# Wifi.net
KiCad netlist of a schematic drawn in Altium Designer
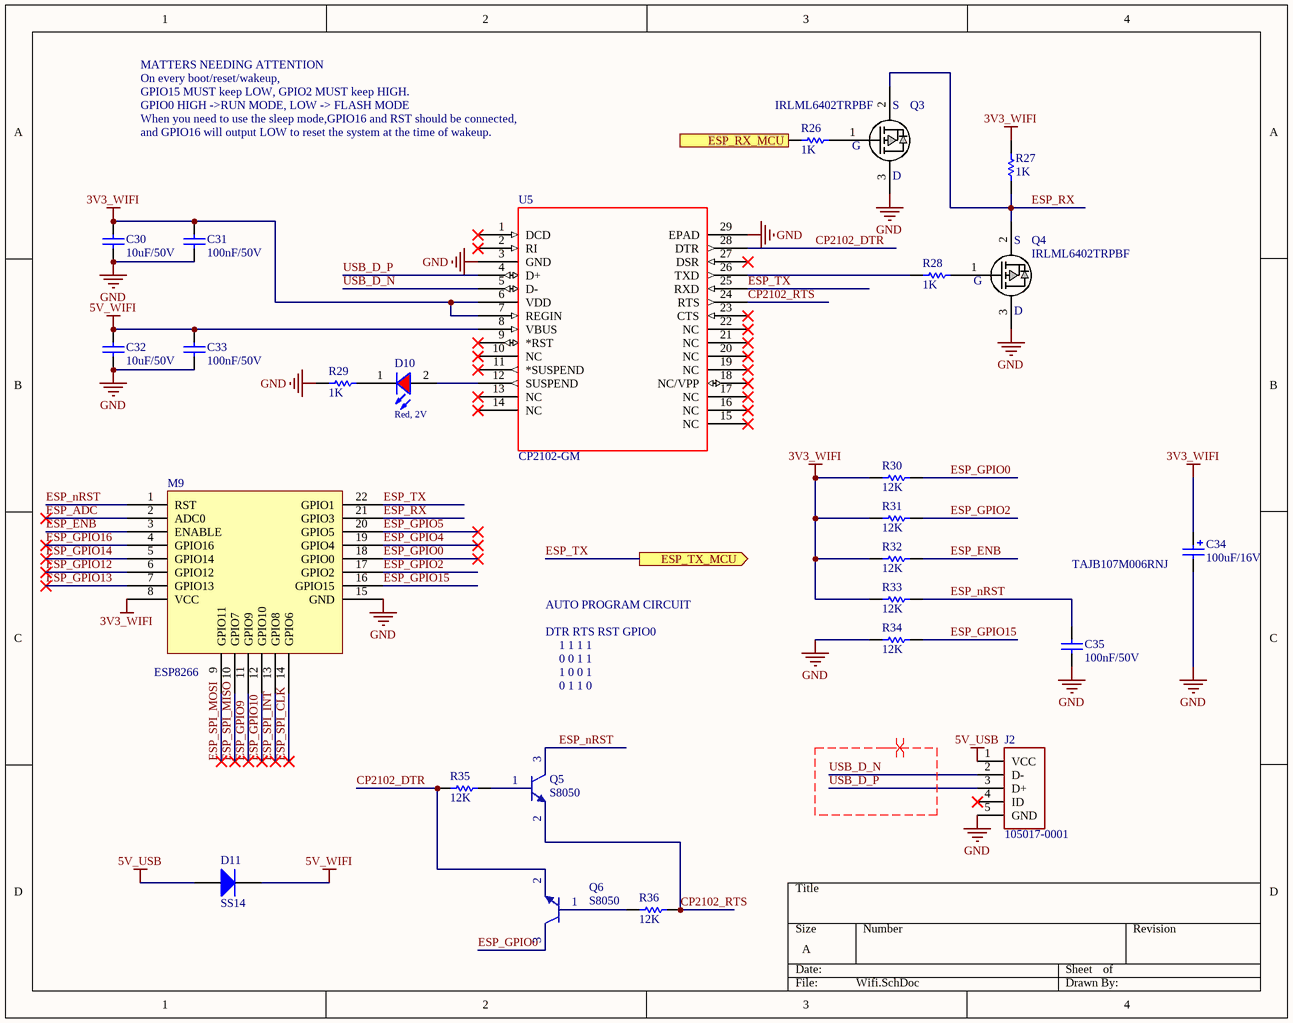
[diagram p0: Wifi.SchDoc]

(export (version "E")
  (design (tool "Eeschema 10.0.6"))
  (components
    (comp (ref "C30")
      (value "10uF/50V")
      (footprint "CAP-SM-0805")
      (description "CAP CER 10UF 50V X5R 0805")
      (fields
        (field (name "MANUFACTURER") "Yageo")
        (field (name "MANUFACTURER PART NUMBER") "CC0805KKX5R9BB106")
      )
      (libsource (lib "Capacitor") (part "Cap-10uF-50V-0805"))
    )
    (comp (ref "C31")
      (value "100nF/50V")
      (footprint "CAP-SM-0805")
      (description "CAP CER 0.1UF 50V Y5V 0805")
      (fields
        (field (name "MANUFACTURER") "Samsung Electro-Mechanics")
        (field (name "MANUFACTURER PART NUMBER") "CL21F104ZBCNNNC")
      )
      (libsource (lib "Capacitor") (part "Cap-100nF-50V-0805"))
    )
    (comp (ref "C32")
      (value "10uF/50V")
      (footprint "CAP-SM-0805")
      (description "CAP CER 10UF 50V X5R 0805")
      (fields
        (field (name "MANUFACTURER") "Yageo")
        (field (name "MANUFACTURER PART NUMBER") "CC0805KKX5R9BB106")
      )
      (libsource (lib "Capacitor") (part "Cap-10uF-50V-0805"))
    )
    (comp (ref "C33")
      (value "100nF/50V")
      (footprint "CAP-SM-0805")
      (description "CAP CER 0.1UF 50V Y5V 0805")
      (fields
        (field (name "MANUFACTURER") "Samsung Electro-Mechanics")
        (field (name "MANUFACTURER PART NUMBER") "CL21F104ZBCNNNC")
      )
      (libsource (lib "Capacitor") (part "Cap-100nF-50V-0805"))
    )
    (comp (ref "C34")
      (value "100uF/16V")
      (footprint "CAP_SM_TAN")
      (fields
        (field (name "MANUFACTURER") "Nichicon")
        (field (name "MANUFACTURER PART NUMBER") "UWX1C101MCL1GB")
        (field (name "Comment") "TAJB107M006RNJ")
      )
      (libsource (lib "Capacitor") (part "Cap-Tan-100uF-16V"))
    )
    (comp (ref "C35")
      (value "100nF/50V")
      (footprint "CAP-SM-0805")
      (description "CAP CER 0.1UF 50V Y5V 0805")
      (fields
        (field (name "MANUFACTURER") "Samsung Electro-Mechanics")
        (field (name "MANUFACTURER PART NUMBER") "CL21F104ZBCNNNC")
      )
      (libsource (lib "Capacitor") (part "Cap-100nF-50V-0805"))
    )
    (comp (ref "D10")
      (value "Red, 2V")
      (footprint "WL-SMCW_0805")
      (description "WL-SMCW SMT Mono-color Chip LED Waterclear, size 0805, Red, 2V, 140deg")
      (fields (field (name "PART NUMBER") "150080RS75000") (field (name "PUBLISHER") "Wurth Elektronik"))
      (libsource (lib "150080BS75000_Altium_WL-SMCW_rev20a") (part "150080RS75000"))
    )
    (comp (ref "D11")
      (value "SS14")
      (footprint "SS14")
      (description "DIODE SCHOTTKY 40V 1A SMA")
      (fields (field (name "MANUFACTURER") "ON Semiconductor"))
      (libsource (lib "Diode") (part "Diode-SS14"))
    )
    (comp (ref "J2")
      (value "105017-0001")
      (footprint "CONN_105017-0001")
      (description "No Description Available")
      (fields (field (name "COPYRIGHT") "Copyright (C) 2018 Accelerated Designs. All rights reserved"))
      (libsource (lib "Header-connector") (part "105017-0001"))
    )
    (comp (ref "M9") (value "ESP8266") (footprint "ESP8266") (libsource (lib "chicken") (part "ESP8266")))
    (comp (ref "Q3")
      (value "IRLML6402TRPBF")
      (footprint "SOT23_NEX")
      (description "P-Channel 20V 3.7A (Ta) 1.3W (Ta) Surface Mount Micro3™/SOT-23")
      (libsource (lib "MOSFET") (part "IRLML6402TRPBF"))
    )
    (comp (ref "Q4")
      (value "IRLML6402TRPBF")
      (footprint "SOT23_NEX")
      (description "P-Channel 20V 3.7A (Ta) 1.3W (Ta) Surface Mount Micro3™/SOT-23")
      (libsource (lib "MOSFET") (part "IRLML6402TRPBF"))
    )
    (comp (ref "Q5") (value "S8050") (footprint "SOT23_NEX") (libsource (lib "BJT") (part "S8050")))
    (comp (ref "Q6") (value "S8050") (footprint "SOT23_NEX") (libsource (lib "BJT") (part "S8050")))
    (comp (ref "R26")
      (value "1K")
      (footprint "Resistor:RES-SM-0805")
      (description "RES 1K OHM 1% 1/4W 0805")
      (fields
        (field (name "MANUFACTURER") "Stackpole Electronics Inc")
        (field (name "MANUFACTURER PART NUMBER") "RNCP0805FTD1K00")
      )
      (libsource (lib "Resistor") (part "Res-1K-0805"))
    )
    (comp (ref "R27")
      (value "1K")
      (footprint "Resistor:RES-SM-0805")
      (description "RES 1K OHM 1% 1/4W 0805")
      (fields
        (field (name "MANUFACTURER") "Stackpole Electronics Inc")
        (field (name "MANUFACTURER PART NUMBER") "RNCP0805FTD1K00")
      )
      (libsource (lib "Resistor") (part "Res-1K-0805"))
    )
    (comp (ref "R28")
      (value "1K")
      (footprint "Resistor:RES-SM-0805")
      (description "RES 1K OHM 1% 1/4W 0805")
      (fields
        (field (name "MANUFACTURER") "Stackpole Electronics Inc")
        (field (name "MANUFACTURER PART NUMBER") "RNCP0805FTD1K00")
      )
      (libsource (lib "Resistor") (part "Res-1K-0805"))
    )
    (comp (ref "R29")
      (value "1K")
      (footprint "Resistor:RES-SM-0805")
      (description "RES 1K OHM 1% 1/4W 0805")
      (fields
        (field (name "MANUFACTURER") "Stackpole Electronics Inc")
        (field (name "MANUFACTURER PART NUMBER") "RNCP0805FTD1K00")
      )
      (libsource (lib "Resistor") (part "Res-1K-0805"))
    )
    (comp (ref "R30")
      (value "12K")
      (footprint "Resistor:RES-SM-0805")
      (description "RES 12 KOHM JUMPER 0805")
      (fields
        (field (name "MANUFACTURER") "Vishay Thin Film")
        (field (name "MANUFACTURER PART NUMBER") "PAT0805E3121BST1")
      )
      (libsource (lib "Resistor") (part "Res-12K-0805"))
    )
    (comp (ref "R31")
      (value "12K")
      (footprint "Resistor:RES-SM-0805")
      (description "RES 12 KOHM JUMPER 0805")
      (fields
        (field (name "MANUFACTURER") "Vishay Thin Film")
        (field (name "MANUFACTURER PART NUMBER") "PAT0805E3121BST1")
      )
      (libsource (lib "Resistor") (part "Res-12K-0805"))
    )
    (comp (ref "R32")
      (value "12K")
      (footprint "Resistor:RES-SM-0805")
      (description "RES 12 KOHM JUMPER 0805")
      (fields
        (field (name "MANUFACTURER") "Vishay Thin Film")
        (field (name "MANUFACTURER PART NUMBER") "PAT0805E3121BST1")
      )
      (libsource (lib "Resistor") (part "Res-12K-0805"))
    )
    (comp (ref "R33")
      (value "12K")
      (footprint "Resistor:RES-SM-0805")
      (description "RES 12 KOHM JUMPER 0805")
      (fields
        (field (name "MANUFACTURER") "Vishay Thin Film")
        (field (name "MANUFACTURER PART NUMBER") "PAT0805E3121BST1")
      )
      (libsource (lib "Resistor") (part "Res-12K-0805"))
    )
    (comp (ref "R34")
      (value "12K")
      (footprint "Resistor:RES-SM-0805")
      (description "RES 12 KOHM JUMPER 0805")
      (fields
        (field (name "MANUFACTURER") "Vishay Thin Film")
        (field (name "MANUFACTURER PART NUMBER") "PAT0805E3121BST1")
      )
      (libsource (lib "Resistor") (part "Res-12K-0805"))
    )
    (comp (ref "R35")
      (value "12K")
      (footprint "Resistor:RES-SM-0805")
      (description "RES 12 KOHM JUMPER 0805")
      (fields
        (field (name "MANUFACTURER") "Vishay Thin Film")
        (field (name "MANUFACTURER PART NUMBER") "PAT0805E3121BST1")
      )
      (libsource (lib "Resistor") (part "Res-12K-0805"))
    )
    (comp (ref "R36")
      (value "12K")
      (footprint "Resistor:RES-SM-0805")
      (description "RES 12 KOHM JUMPER 0805")
      (fields
        (field (name "MANUFACTURER") "Vishay Thin Film")
        (field (name "MANUFACTURER PART NUMBER") "PAT0805E3121BST1")
      )
      (libsource (lib "Resistor") (part "Res-12K-0805"))
    )
    (comp (ref "U5")
      (value "CP2102-GM")
      (footprint "CP2102-GM")
      (description "No Description Available")
      (fields (field (name "COPYRIGHT") "Copyright (C) 2018 Accelerated Designs. All rights reserved"))
      (libsource (lib "chicken") (part "CP2102-GM"))
    )
  )
  (nets
    (net (code "1") (name "/CP2102_DTR") (class "Default")
      (node (ref "Q6") (pin "2") (pinfunction "E_2") (pintype "passive"))
      (node (ref "R35") (pin "1") (pinfunction "1_1") (pintype "passive"))
      (node (ref "U5") (pin "28") (pinfunction "DTR_28") (pintype "output"))
    )
    (net (code "2") (name "/CP2102_RTS") (class "Default")
      (node (ref "Q5") (pin "2") (pinfunction "E_2") (pintype "passive"))
      (node (ref "R36") (pin "2") (pinfunction "2_2") (pintype "passive"))
      (node (ref "U5") (pin "24") (pinfunction "RTS_24") (pintype "output"))
    )
    (net (code "3") (name "/ESP_ADC") (class "Default")
      (node (ref "M9") (pin "2") (pinfunction "ADC0_2") (pintype "passive+no_connect"))
    )
    (net (code "4") (name "/ESP_ENB") (class "Default")
      (node (ref "M9") (pin "3") (pinfunction "ENABLE_3") (pintype "passive"))
      (node (ref "R32") (pin "2") (pinfunction "2_2") (pintype "passive"))
    )
    (net (code "5") (name "/ESP_GPIO0") (class "Default")
      (node (ref "M9") (pin "18") (pinfunction "GPIO0_18") (pintype "passive"))
      (node (ref "Q6") (pin "3") (pinfunction "C_3") (pintype "passive"))
      (node (ref "R30") (pin "2") (pinfunction "2_2") (pintype "passive"))
    )
    (net (code "6") (name "/ESP_GPIO2") (class "Default")
      (node (ref "M9") (pin "17") (pinfunction "GPIO2_17") (pintype "passive"))
      (node (ref "R31") (pin "2") (pinfunction "2_2") (pintype "passive"))
    )
    (net (code "7") (name "/ESP_GPIO4") (class "Default")
      (node (ref "M9") (pin "19") (pinfunction "GPIO4_19") (pintype "passive+no_connect"))
    )
    (net (code "8") (name "/ESP_GPIO5") (class "Default")
      (node (ref "M9") (pin "20") (pinfunction "GPIO5_20") (pintype "passive+no_connect"))
    )
    (net (code "9") (name "/ESP_GPIO9") (class "Default")
      (node (ref "M9") (pin "11") (pinfunction "GPIO9_11") (pintype "passive+no_connect"))
    )
    (net (code "10") (name "/ESP_GPIO10") (class "Default")
      (node (ref "M9") (pin "12") (pinfunction "GPIO10_12") (pintype "passive+no_connect"))
    )
    (net (code "11") (name "/ESP_GPIO12") (class "Default")
      (node (ref "M9") (pin "6") (pinfunction "GPIO12_6") (pintype "passive+no_connect"))
    )
    (net (code "12") (name "/ESP_GPIO13") (class "Default")
      (node (ref "M9") (pin "7") (pinfunction "GPIO13_7") (pintype "passive+no_connect"))
    )
    (net (code "13") (name "/ESP_GPIO14") (class "Default")
      (node (ref "M9") (pin "5") (pinfunction "GPIO14_5") (pintype "passive+no_connect"))
    )
    (net (code "14") (name "/ESP_GPIO15") (class "Default")
      (node (ref "M9") (pin "16") (pinfunction "GPIO15_16") (pintype "passive"))
      (node (ref "R34") (pin "2") (pinfunction "2_2") (pintype "passive"))
    )
    (net (code "15") (name "/ESP_GPIO16") (class "Default")
      (node (ref "M9") (pin "4") (pinfunction "GPIO16_4") (pintype "passive+no_connect"))
    )
    (net (code "16") (name "/ESP_RX") (class "Default")
      (node (ref "M9") (pin "21") (pinfunction "GPIO3_21") (pintype "passive"))
      (node (ref "Q3") (pin "2") (pinfunction "S_2") (pintype "passive"))
      (node (ref "Q4") (pin "2") (pinfunction "S_2") (pintype "passive"))
      (node (ref "R27") (pin "1") (pinfunction "1_1") (pintype "passive"))
    )
    (net (code "17") (name "/ESP_RX_MCU") (class "Default")
      (node (ref "R26") (pin "2") (pinfunction "2_2") (pintype "passive"))
    )
    (net (code "18") (name "/ESP_SPI_CLK") (class "Default")
      (node (ref "M9") (pin "14") (pinfunction "GPIO6_14") (pintype "passive+no_connect"))
    )
    (net (code "19") (name "/ESP_SPI_INT") (class "Default")
      (node (ref "M9") (pin "13") (pinfunction "GPIO8_13") (pintype "passive+no_connect"))
    )
    (net (code "20") (name "/ESP_SPI_MISO") (class "Default")
      (node (ref "M9") (pin "10") (pinfunction "GPIO7_10") (pintype "passive+no_connect"))
    )
    (net (code "21") (name "/ESP_SPI_MOSI") (class "Default")
      (node (ref "M9") (pin "9") (pinfunction "GPIO11_9") (pintype "passive+no_connect"))
    )
    (net (code "22") (name "/ESP_TX") (class "Default")
      (node (ref "M9") (pin "22") (pinfunction "GPIO1_22") (pintype "passive"))
      (node (ref "U5") (pin "25") (pinfunction "RXD_25") (pintype "input"))
    )
    (net (code "23") (name "/ESP_nRST") (class "Default")
      (node (ref "C35") (pin "2") (pinfunction "2_2") (pintype "passive"))
      (node (ref "M9") (pin "1") (pinfunction "RST_1") (pintype "passive"))
      (node (ref "Q5") (pin "3") (pinfunction "C_3") (pintype "passive"))
      (node (ref "R33") (pin "2") (pinfunction "2_2") (pintype "passive"))
    )
    (net (code "24") (name "/USB_D_N") (class "Default")
      (node (ref "J2") (pin "2") (pinfunction "D-_2") (pintype "passive"))
      (node (ref "U5") (pin "5") (pinfunction "D-_5") (pintype "bidirectional"))
    )
    (net (code "25") (name "/USB_D_P") (class "Default")
      (node (ref "J2") (pin "3") (pinfunction "D+_3") (pintype "passive"))
      (node (ref "U5") (pin "4") (pinfunction "D+_4") (pintype "bidirectional"))
    )
    (net (code "26") (name "3V3_WIFI") (class "Default")
      (node (ref "C30") (pin "2") (pinfunction "2_2") (pintype "passive"))
      (node (ref "C31") (pin "2") (pinfunction "2_2") (pintype "passive"))
      (node (ref "C34") (pin "1") (pinfunction "1_1") (pintype "passive"))
      (node (ref "M9") (pin "8") (pinfunction "VCC_8") (pintype "passive"))
      (node (ref "R27") (pin "2") (pinfunction "2_2") (pintype "passive"))
      (node (ref "R30") (pin "1") (pinfunction "1_1") (pintype "passive"))
      (node (ref "R31") (pin "1") (pinfunction "1_1") (pintype "passive"))
      (node (ref "R32") (pin "1") (pinfunction "1_1") (pintype "passive"))
      (node (ref "R33") (pin "1") (pinfunction "1_1") (pintype "passive"))
      (node (ref "U5") (pin "6") (pinfunction "VDD_6") (pintype "power_in"))
      (node (ref "U5") (pin "7") (pinfunction "REGIN_7") (pintype "input"))
    )
    (net (code "27") (name "5V_USB") (class "Default")
      (node (ref "D11") (pin "2") (pinfunction "A_2") (pintype "passive"))
      (node (ref "J2") (pin "1") (pinfunction "VCC_1") (pintype "passive"))
    )
    (net (code "28") (name "5V_WIFI") (class "Default")
      (node (ref "C32") (pin "2") (pinfunction "2_2") (pintype "passive"))
      (node (ref "C33") (pin "2") (pinfunction "2_2") (pintype "passive"))
      (node (ref "D11") (pin "1") (pinfunction "K_1") (pintype "passive"))
      (node (ref "U5") (pin "8") (pinfunction "VBUS_8") (pintype "input"))
    )
    (net (code "29") (name "GND") (class "Default")
      (node (ref "C30") (pin "1") (pinfunction "1_1") (pintype "passive"))
      (node (ref "C31") (pin "1") (pinfunction "1_1") (pintype "passive"))
      (node (ref "C32") (pin "1") (pinfunction "1_1") (pintype "passive"))
      (node (ref "C33") (pin "1") (pinfunction "1_1") (pintype "passive"))
      (node (ref "C34") (pin "2") (pinfunction "2_2") (pintype "passive"))
      (node (ref "C35") (pin "1") (pinfunction "1_1") (pintype "passive"))
      (node (ref "J2") (pin "5") (pinfunction "GND_5") (pintype "passive"))
      (node (ref "M9") (pin "15") (pinfunction "GND_15") (pintype "passive"))
      (node (ref "Q3") (pin "3") (pinfunction "D_3") (pintype "passive"))
      (node (ref "Q4") (pin "3") (pinfunction "D_3") (pintype "passive"))
      (node (ref "R29") (pin "1") (pinfunction "1_1") (pintype "passive"))
      (node (ref "R34") (pin "1") (pinfunction "1_1") (pintype "passive"))
      (node (ref "U5") (pin "29") (pinfunction "EPAD_29") (pintype "passive"))
      (node (ref "U5") (pin "3") (pinfunction "GND_3") (pintype "power_in"))
    )
    (net (code "30") (name "Net-(D10-A)") (class "Default")
      (node (ref "D10") (pin "2") (pinfunction "A_2") (pintype "passive"))
      (node (ref "U5") (pin "12") (pinfunction "SUSPEND_12") (pintype "output"))
    )
    (net (code "31") (name "Net-(D10-K)") (class "Default")
      (node (ref "D10") (pin "1") (pinfunction "K_1") (pintype "passive"))
      (node (ref "R29") (pin "2") (pinfunction "2_2") (pintype "passive"))
    )
    (net (code "32") (name "Net-(Q3-G)") (class "Default")
      (node (ref "Q3") (pin "1") (pinfunction "G_1") (pintype "passive"))
      (node (ref "R26") (pin "1") (pinfunction "1_1") (pintype "passive"))
    )
    (net (code "33") (name "Net-(Q4-G)") (class "Default")
      (node (ref "Q4") (pin "1") (pinfunction "G_1") (pintype "passive"))
      (node (ref "R28") (pin "2") (pinfunction "2_2") (pintype "passive"))
    )
    (net (code "34") (name "Net-(Q5-B)") (class "Default")
      (node (ref "Q5") (pin "1") (pinfunction "B_1") (pintype "passive"))
      (node (ref "R35") (pin "2") (pinfunction "2_2") (pintype "passive"))
    )
    (net (code "35") (name "Net-(Q6-B)") (class "Default")
      (node (ref "Q6") (pin "1") (pinfunction "B_1") (pintype "passive"))
      (node (ref "R36") (pin "1") (pinfunction "1_1") (pintype "passive"))
    )
    (net (code "36") (name "Net-(U5-TXD)") (class "Default")
      (node (ref "R28") (pin "1") (pinfunction "1_1") (pintype "passive"))
      (node (ref "U5") (pin "26") (pinfunction "TXD_26") (pintype "output"))
    )
    (net (code "37") (name "unconnected-(J2-ID-Pad4)") (class "Default")
      (node (ref "J2") (pin "4") (pinfunction "ID_4") (pintype "passive+no_connect"))
    )
    (net (code "38") (name "unconnected-(U5-*RST-Pad9)") (class "Default")
      (node (ref "U5") (pin "9") (pinfunction "*RST_9") (pintype "bidirectional+no_connect"))
    )
    (net (code "39") (name "unconnected-(U5-*SUSPEND-Pad11)") (class "Default")
      (node (ref "U5") (pin "11") (pinfunction "*SUSPEND_11") (pintype "output+no_connect"))
    )
    (net (code "40") (name "unconnected-(U5-CTS-Pad23)") (class "Default")
      (node (ref "U5") (pin "23") (pinfunction "CTS_23") (pintype "input+no_connect"))
    )
    (net (code "41") (name "unconnected-(U5-DCD-Pad1)") (class "Default")
      (node (ref "U5") (pin "1") (pinfunction "DCD_1") (pintype "input+no_connect"))
    )
    (net (code "42") (name "unconnected-(U5-DSR-Pad27)") (class "Default")
      (node (ref "U5") (pin "27") (pinfunction "DSR_27") (pintype "input+no_connect"))
    )
    (net (code "43") (name "unconnected-(U5-NC-Pad10)") (class "Default")
      (node (ref "U5") (pin "10") (pinfunction "NC_10") (pintype "passive+no_connect"))
    )
    (net (code "44") (name "unconnected-(U5-NC-Pad13)") (class "Default")
      (node (ref "U5") (pin "13") (pinfunction "NC_13") (pintype "passive+no_connect"))
    )
    (net (code "45") (name "unconnected-(U5-NC-Pad14)") (class "Default")
      (node (ref "U5") (pin "14") (pinfunction "NC_14") (pintype "passive+no_connect"))
    )
    (net (code "46") (name "unconnected-(U5-NC-Pad15)") (class "Default")
      (node (ref "U5") (pin "15") (pinfunction "NC_15") (pintype "passive+no_connect"))
    )
    (net (code "47") (name "unconnected-(U5-NC-Pad16)") (class "Default")
      (node (ref "U5") (pin "16") (pinfunction "NC_16") (pintype "passive+no_connect"))
    )
    (net (code "48") (name "unconnected-(U5-NC-Pad17)") (class "Default")
      (node (ref "U5") (pin "17") (pinfunction "NC_17") (pintype "passive+no_connect"))
    )
    (net (code "49") (name "unconnected-(U5-NC-Pad19)") (class "Default")
      (node (ref "U5") (pin "19") (pinfunction "NC_19") (pintype "passive+no_connect"))
    )
    (net (code "50") (name "unconnected-(U5-NC-Pad20)") (class "Default")
      (node (ref "U5") (pin "20") (pinfunction "NC_20") (pintype "passive+no_connect"))
    )
    (net (code "51") (name "unconnected-(U5-NC-Pad21)") (class "Default")
      (node (ref "U5") (pin "21") (pinfunction "NC_21") (pintype "passive+no_connect"))
    )
    (net (code "52") (name "unconnected-(U5-NC-Pad22)") (class "Default")
      (node (ref "U5") (pin "22") (pinfunction "NC_22") (pintype "passive+no_connect"))
    )
    (net (code "53") (name "unconnected-(U5-NC{slash}VPP-Pad18)") (class "Default")
      (node (ref "U5") (pin "18") (pinfunction "NC/VPP_18") (pintype "bidirectional+no_connect"))
    )
    (net (code "54") (name "unconnected-(U5-RI-Pad2)") (class "Default")
      (node (ref "U5") (pin "2") (pinfunction "RI_2") (pintype "input+no_connect"))
    )
  )
)
